# diff2se.net
KiCad netlist of a schematic drawn in EAGLE
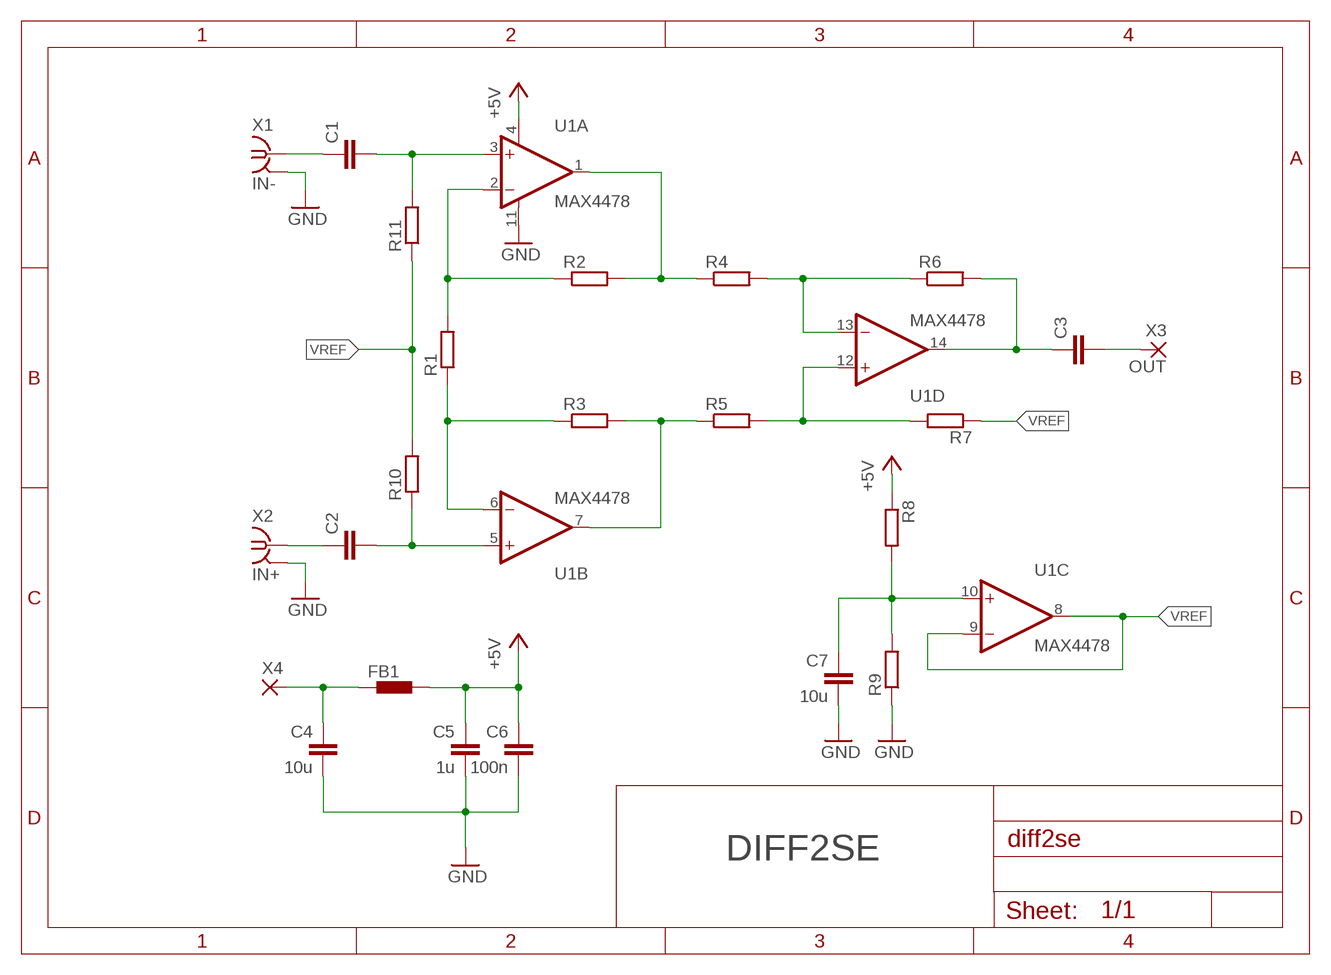
[diagram p0: schematic, sheet 1]

(export (version "E")
  (design (tool "Eeschema 10.0.6"))
  (components
    (comp (ref "C1")
      (value "C-EUC0805K")
      (footprint "eagle-import:C0805K")
      (libsource (lib "eagle-import") (part "C-EUC0805K"))
    )
    (comp (ref "C2")
      (value "C-EUC0805K")
      (footprint "eagle-import:C0805K")
      (libsource (lib "eagle-import") (part "C-EUC0805K"))
    )
    (comp (ref "C3")
      (value "C-EUC0805K")
      (footprint "eagle-import:C0805K")
      (libsource (lib "eagle-import") (part "C-EUC0805K"))
    )
    (comp (ref "C4")
      (value "10u")
      (footprint "eagle-import:C0805K")
      (libsource (lib "eagle-import") (part "C-EUC0805K"))
    )
    (comp (ref "C5")
      (value "1u")
      (footprint "eagle-import:C0805K")
      (libsource (lib "eagle-import") (part "C-EUC0805K"))
    )
    (comp (ref "C6")
      (value "100n")
      (footprint "eagle-import:C0805K")
      (libsource (lib "eagle-import") (part "C-EUC0805K"))
    )
    (comp (ref "C7")
      (value "10u")
      (footprint "eagle-import:C0402")
      (libsource (lib "eagle-import") (part "C-EUC0402"))
    )
    (comp (ref "FB1")
      (value "BML15H")
      (footprint "eagle-import:R0603")
      (libsource (lib "eagle-import") (part "BML15H"))
    )
    (comp (ref "R1")
      (value "R-EU_WSC01/2")
      (footprint "eagle-import:WSC01_2")
      (libsource (lib "eagle-import") (part "R-EU_WSC01/2"))
    )
    (comp (ref "R2")
      (value "R-EU_R0805")
      (footprint "eagle-import:R0805")
      (libsource (lib "eagle-import") (part "R-EU_R0805"))
    )
    (comp (ref "R3")
      (value "R-EU_R0805")
      (footprint "eagle-import:R0805")
      (libsource (lib "eagle-import") (part "R-EU_R0805"))
    )
    (comp (ref "R4")
      (value "R-EU_R0805")
      (footprint "eagle-import:R0805")
      (libsource (lib "eagle-import") (part "R-EU_R0805"))
    )
    (comp (ref "R5")
      (value "R-EU_R0805")
      (footprint "eagle-import:R0805")
      (libsource (lib "eagle-import") (part "R-EU_R0805"))
    )
    (comp (ref "R6")
      (value "R-EU_R0805")
      (footprint "eagle-import:R0805")
      (libsource (lib "eagle-import") (part "R-EU_R0805"))
    )
    (comp (ref "R7")
      (value "R-EU_R0805")
      (footprint "eagle-import:R0805")
      (libsource (lib "eagle-import") (part "R-EU_R0805"))
    )
    (comp (ref "R8")
      (value "R-EU_R0402")
      (footprint "eagle-import:R0402")
      (libsource (lib "eagle-import") (part "R-EU_R0402"))
    )
    (comp (ref "R9")
      (value "R-EU_R0402")
      (footprint "eagle-import:R0402")
      (libsource (lib "eagle-import") (part "R-EU_R0402"))
    )
    (comp (ref "R10")
      (value "R-EU_R0402")
      (footprint "eagle-import:R0402")
      (libsource (lib "eagle-import") (part "R-EU_R0402"))
    )
    (comp (ref "R11")
      (value "R-EU_R0402")
      (footprint "eagle-import:R0402")
      (libsource (lib "eagle-import") (part "R-EU_R0402"))
    )
    (comp (ref "U1")
      (value "MAX4478")
      (footprint "eagle-import:SO14")
      (fields (field (name "MF") "TEXAS INSTRUMENTS") (field (name "MPN") "OPA4130UA"))
      (libsource (lib "eagle-import") (part "OPA4130U"))
    )
    (comp (ref "X1")
      (value "IN-")
      (footprint "eagle-import:J502-ND-142-0701-881_886")
      (fields (field (name "MF") "JOHNSON COMPONENTS") (field (name "MPN") "142-0701-881"))
      (libsource (lib "eagle-import") (part "SMA-142-0701-881/886"))
    )
    (comp (ref "X2")
      (value "IN+")
      (footprint "eagle-import:J502-ND-142-0701-881_886")
      (fields (field (name "MF") "JOHNSON COMPONENTS") (field (name "MPN") "142-0701-881"))
      (libsource (lib "eagle-import") (part "SMA-142-0701-881/886"))
    )
    (comp (ref "X3")
      (value "OUT")
      (footprint "eagle-import:SMD1,27-2,54")
      (libsource (lib "eagle-import") (part "SMD2"))
    )
    (comp (ref "X4")
      (value "SMD2")
      (footprint "eagle-import:SMD1,27-2,54")
      (libsource (lib "eagle-import") (part "SMD2"))
    )
  )
  (nets
    (net (code "1") (name "+5V") (class "Default")
      (node (ref "C5") (pin "1") (pinfunction "1_1") (pintype "passive"))
      (node (ref "C6") (pin "1") (pinfunction "1_1") (pintype "passive"))
      (node (ref "FB1") (pin "2") (pinfunction "2_2") (pintype "passive"))
      (node (ref "R8") (pin "1") (pinfunction "1_1") (pintype "passive"))
      (node (ref "U1") (pin "4") (pinfunction "V+_4") (pintype "power_in"))
    )
    (net (code "2") (name "GND") (class "Default")
      (node (ref "C4") (pin "2") (pinfunction "2_2") (pintype "passive"))
      (node (ref "C5") (pin "2") (pinfunction "2_2") (pintype "passive"))
      (node (ref "C6") (pin "2") (pinfunction "2_2") (pintype "passive"))
      (node (ref "C7") (pin "2") (pinfunction "2_2") (pintype "passive"))
      (node (ref "R9") (pin "1") (pinfunction "1_1") (pintype "passive"))
      (node (ref "U1") (pin "11") (pinfunction "V-_11") (pintype "power_in"))
      (node (ref "X1") (pin "G@1") (pinfunction "GND_G@1") (pintype "power_in"))
      (node (ref "X2") (pin "G@1") (pinfunction "GND_G@1") (pintype "power_in"))
    )
    (net (code "3") (name "Net-(C1-Pad1)") (class "Default")
      (node (ref "C1") (pin "1") (pinfunction "1_1") (pintype "passive"))
      (node (ref "X1") (pin "1") (pinfunction "1_1") (pintype "passive"))
    )
    (net (code "4") (name "Net-(C2-Pad1)") (class "Default")
      (node (ref "C2") (pin "1") (pinfunction "1_1") (pintype "passive"))
      (node (ref "X2") (pin "1") (pinfunction "1_1") (pintype "passive"))
    )
    (net (code "5") (name "Net-(U1A-+IN)") (class "Default")
      (node (ref "C1") (pin "2") (pinfunction "2_2") (pintype "passive"))
      (node (ref "R11") (pin "2") (pinfunction "2_2") (pintype "passive"))
      (node (ref "U1") (pin "3") (pinfunction "+IN_3") (pintype "input"))
    )
    (net (code "6") (name "Net-(U1A--IN)") (class "Default")
      (node (ref "R1") (pin "2") (pinfunction "2_2") (pintype "passive"))
      (node (ref "R2") (pin "1") (pinfunction "1_1") (pintype "passive"))
      (node (ref "U1") (pin "2") (pinfunction "-IN_2") (pintype "input"))
    )
    (net (code "7") (name "Net-(U1A-OUT)") (class "Default")
      (node (ref "R2") (pin "2") (pinfunction "2_2") (pintype "passive"))
      (node (ref "R4") (pin "1") (pinfunction "1_1") (pintype "passive"))
      (node (ref "U1") (pin "1") (pinfunction "OUT_1") (pintype "output"))
    )
    (net (code "8") (name "Net-(U1B-+IN)") (class "Default")
      (node (ref "C2") (pin "2") (pinfunction "2_2") (pintype "passive"))
      (node (ref "R10") (pin "1") (pinfunction "1_1") (pintype "passive"))
      (node (ref "U1") (pin "5") (pinfunction "+IN_5") (pintype "input"))
    )
    (net (code "9") (name "Net-(U1B--IN)") (class "Default")
      (node (ref "R1") (pin "1") (pinfunction "1_1") (pintype "passive"))
      (node (ref "R3") (pin "1") (pinfunction "1_1") (pintype "passive"))
      (node (ref "U1") (pin "6") (pinfunction "-IN_6") (pintype "input"))
    )
    (net (code "10") (name "Net-(U1B-OUT)") (class "Default")
      (node (ref "R3") (pin "2") (pinfunction "2_2") (pintype "passive"))
      (node (ref "R5") (pin "1") (pinfunction "1_1") (pintype "passive"))
      (node (ref "U1") (pin "7") (pinfunction "OUT_7") (pintype "output"))
    )
    (net (code "11") (name "Net-(U1C-+IN)") (class "Default")
      (node (ref "C7") (pin "1") (pinfunction "1_1") (pintype "passive"))
      (node (ref "R8") (pin "2") (pinfunction "2_2") (pintype "passive"))
      (node (ref "R9") (pin "2") (pinfunction "2_2") (pintype "passive"))
      (node (ref "U1") (pin "10") (pinfunction "+IN_10") (pintype "input"))
    )
    (net (code "12") (name "Net-(U1D-+IN)") (class "Default")
      (node (ref "R5") (pin "2") (pinfunction "2_2") (pintype "passive"))
      (node (ref "R7") (pin "2") (pinfunction "2_2") (pintype "passive"))
      (node (ref "U1") (pin "12") (pinfunction "+IN_12") (pintype "input"))
    )
    (net (code "13") (name "Net-(U1D--IN)") (class "Default")
      (node (ref "R4") (pin "2") (pinfunction "2_2") (pintype "passive"))
      (node (ref "R6") (pin "1") (pinfunction "1_1") (pintype "passive"))
      (node (ref "U1") (pin "13") (pinfunction "-IN_13") (pintype "input"))
    )
    (net (code "14") (name "Net-(U1D-OUT)") (class "Default")
      (node (ref "C3") (pin "1") (pinfunction "1_1") (pintype "passive"))
      (node (ref "R6") (pin "2") (pinfunction "2_2") (pintype "passive"))
      (node (ref "U1") (pin "14") (pinfunction "OUT_14") (pintype "output"))
    )
    (net (code "15") (name "Net-(X3-P)") (class "Default")
      (node (ref "C3") (pin "2") (pinfunction "2_2") (pintype "passive"))
      (node (ref "X3") (pin "1") (pinfunction "P_1") (pintype "passive"))
    )
    (net (code "16") (name "Net-(X4-P)") (class "Default")
      (node (ref "C4") (pin "1") (pinfunction "1_1") (pintype "passive"))
      (node (ref "FB1") (pin "1") (pinfunction "1_1") (pintype "passive"))
      (node (ref "X4") (pin "1") (pinfunction "P_1") (pintype "passive"))
    )
    (net (code "17") (name "VREF") (class "Default")
      (node (ref "R10") (pin "2") (pinfunction "2_2") (pintype "passive"))
      (node (ref "R11") (pin "1") (pinfunction "1_1") (pintype "passive"))
      (node (ref "R7") (pin "1") (pinfunction "1_1") (pintype "passive"))
      (node (ref "U1") (pin "8") (pinfunction "OUT_8") (pintype "output"))
      (node (ref "U1") (pin "9") (pinfunction "-IN_9") (pintype "input"))
    )
  )
)
